# QRE1113_Line_Sensor_Breakout_-_Analog.net
KiCad netlist of a schematic drawn in EAGLE
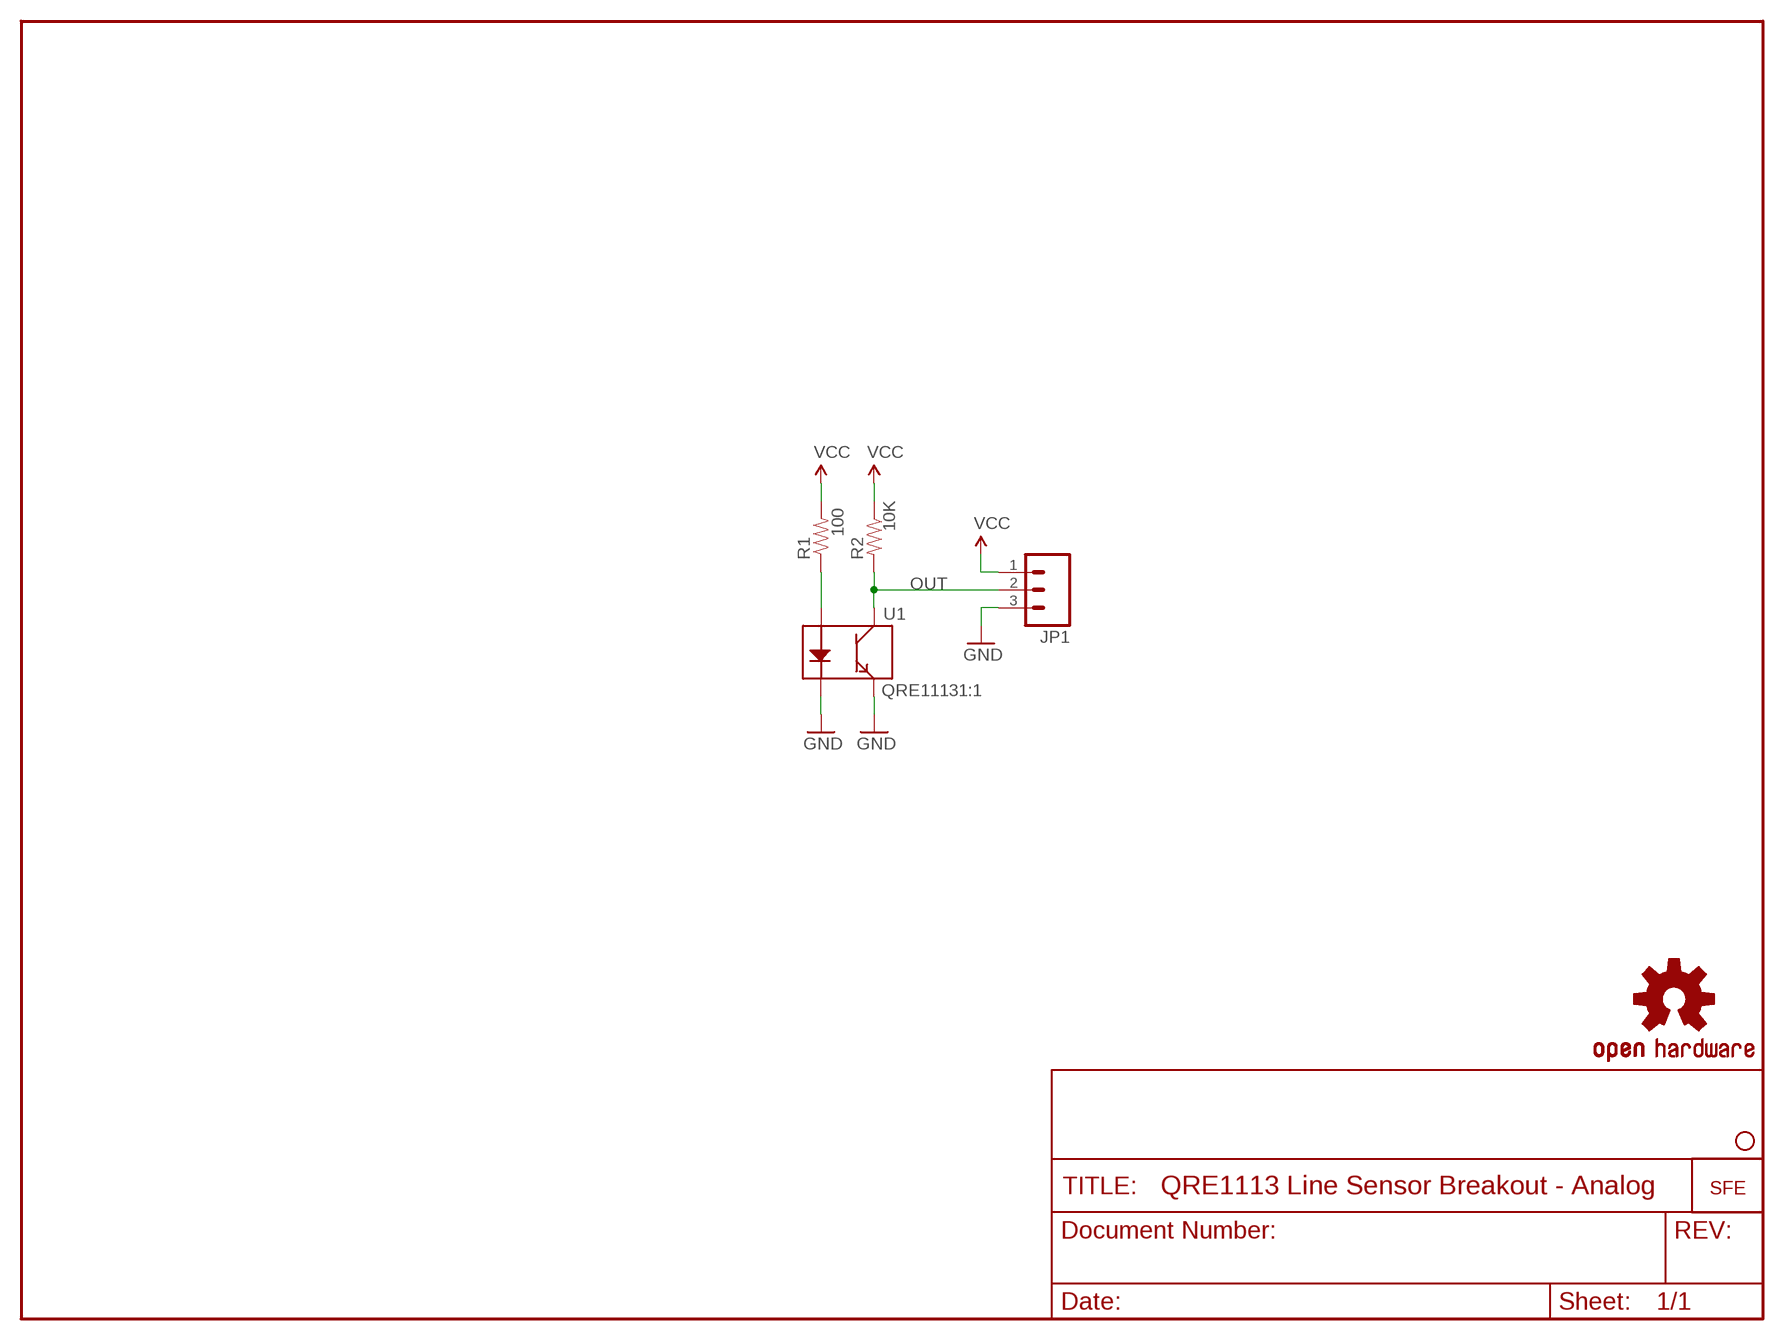
[diagram p0: schematic, sheet 1]

(export (version "E")
  (design (tool "Eeschema 10.0.6"))
  (components
    (comp (ref "JP1")
      (value "M03PTH")
      (footprint "eagle-import:1X03")
      (libsource (lib "eagle-import") (part "M03PTH"))
    )
    (comp (ref "JP2")
      (value "LOGO-SFESK")
      (footprint "eagle-import:SFE-LOGO-FLAME")
      (libsource (lib "eagle-import") (part "LOGO-SFESK"))
    )
    (comp (ref "JP3")
      (value "STAND-OFF")
      (footprint "eagle-import:STAND-OFF")
      (libsource (lib "eagle-import") (part "STAND-OFF"))
    )
    (comp (ref "R1")
      (value "100")
      (footprint "eagle-import:0603-RES")
      (libsource (lib "eagle-import") (part "RESISTOR0603-RES"))
    )
    (comp (ref "R2")
      (value "10K")
      (footprint "eagle-import:0603-RES")
      (libsource (lib "eagle-import") (part "RESISTOR0603-RES"))
    )
    (comp (ref "U$1")
      (value "OSHW-LOGOS")
      (footprint "eagle-import:OSHW-LOGO-S")
      (libsource (lib "eagle-import") (part "OSHW-LOGOS"))
    )
    (comp (ref "U1")
      (value "QRE11131:1")
      (footprint "eagle-import:QRE1113-1_1")
      (libsource (lib "eagle-import") (part "QRE11131{colon}1"))
    )
  )
  (nets
    (net (code "1") (name "/OUT") (class "Default")
      (node (ref "JP1") (pin "2") (pinfunction "2_2") (pintype "passive"))
      (node (ref "R2") (pin "2") (pinfunction "2_2") (pintype "passive"))
      (node (ref "U1") (pin "3") (pinfunction "C_3") (pintype "bidirectional"))
    )
    (net (code "2") (name "GND") (class "Default")
      (node (ref "JP1") (pin "3") (pinfunction "3_3") (pintype "passive"))
      (node (ref "U1") (pin "2") (pinfunction "K_2") (pintype "bidirectional"))
      (node (ref "U1") (pin "4") (pinfunction "E_4") (pintype "bidirectional"))
    )
    (net (code "3") (name "Net-(U1-A)") (class "Default")
      (node (ref "R1") (pin "1") (pinfunction "1_1") (pintype "passive"))
      (node (ref "U1") (pin "1") (pinfunction "A_1") (pintype "bidirectional"))
    )
    (net (code "4") (name "VCC") (class "Default")
      (node (ref "JP1") (pin "1") (pinfunction "1_1") (pintype "passive"))
      (node (ref "R1") (pin "2") (pinfunction "2_2") (pintype "passive"))
      (node (ref "R2") (pin "1") (pinfunction "1_1") (pintype "passive"))
    )
  )
)
